# Controller.net
KiCad netlist of a schematic drawn in EAGLE
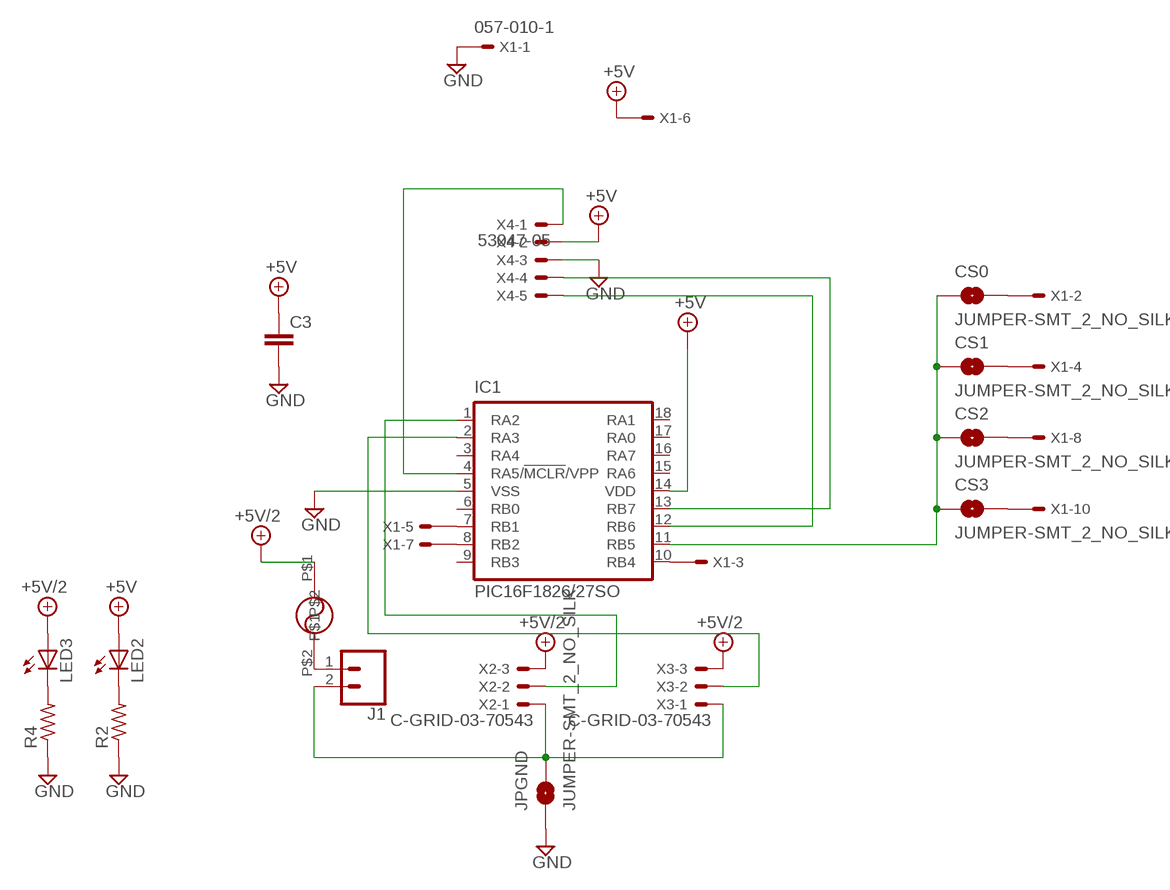
[diagram p0: schematic, sheet 1]

(export (version "E")
  (design (tool "Eeschema 10.0.6"))
  (components
    (comp (ref "C3")
      (value "C-EUC1206")
      (footprint "eagle-import:C1206")
      (libsource (lib "eagle-import") (part "C-EUC1206"))
    )
    (comp (ref "CS0")
      (value "JUMPER-SMT_2_NO_SILK")
      (footprint "eagle-import:SMT-JUMPER_2_NO_SILK")
      (libsource (lib "eagle-import") (part "JUMPER-SMT_2_NO_SILK"))
    )
    (comp (ref "CS1")
      (value "JUMPER-SMT_2_NO_SILK")
      (footprint "eagle-import:SMT-JUMPER_2_NO_SILK")
      (libsource (lib "eagle-import") (part "JUMPER-SMT_2_NO_SILK"))
    )
    (comp (ref "CS2")
      (value "JUMPER-SMT_2_NO_SILK")
      (footprint "eagle-import:SMT-JUMPER_2_NO_SILK")
      (libsource (lib "eagle-import") (part "JUMPER-SMT_2_NO_SILK"))
    )
    (comp (ref "CS3")
      (value "JUMPER-SMT_2_NO_SILK")
      (footprint "eagle-import:SMT-JUMPER_2_NO_SILK")
      (libsource (lib "eagle-import") (part "JUMPER-SMT_2_NO_SILK"))
    )
    (comp (ref "IC1")
      (value "PIC16F1826/27SO")
      (footprint "eagle-import:SO-18W")
      (libsource (lib "eagle-import") (part "PIC16F1826/27SO"))
    )
    (comp (ref "J1")
      (value "CONN_023.5MM")
      (footprint "eagle-import:SCREWTERMINAL-3.5MM-2")
      (libsource (lib "eagle-import") (part "CONN_023.5MM"))
    )
    (comp (ref "JPGND")
      (value "JUMPER-SMT_2_NO_SILK")
      (footprint "eagle-import:SMT-JUMPER_2_NO_SILK")
      (libsource (lib "eagle-import") (part "JUMPER-SMT_2_NO_SILK"))
    )
    (comp (ref "LED2")
      (value "LEDCHIPLED_1206")
      (footprint "eagle-import:CHIPLED_1206")
      (libsource (lib "eagle-import") (part "LEDCHIPLED_1206"))
    )
    (comp (ref "LED3")
      (value "LEDCHIPLED_1206")
      (footprint "eagle-import:CHIPLED_1206")
      (libsource (lib "eagle-import") (part "LEDCHIPLED_1206"))
    )
    (comp (ref "R2")
      (value "R-US_R1206")
      (footprint "eagle-import:R1206")
      (libsource (lib "eagle-import") (part "R-US_R1206"))
    )
    (comp (ref "R4")
      (value "R-US_R1206")
      (footprint "eagle-import:R1206")
      (libsource (lib "eagle-import") (part "R-US_R1206"))
    )
    (comp (ref "U$3")
      (value "0034.6081")
      (footprint "eagle-import:MSF250")
      (libsource (lib "eagle-import") (part "0034.6081"))
    )
    (comp (ref "X1")
      (value "057-010-1")
      (footprint "eagle-import:057-010-1")
      (libsource (lib "eagle-import") (part "057-010-1"))
    )
    (comp (ref "X2")
      (value "C-GRID-03-70543")
      (footprint "eagle-import:70543-03")
      (libsource (lib "eagle-import") (part "C-GRID-03-70543"))
    )
    (comp (ref "X3")
      (value "C-GRID-03-70543")
      (footprint "eagle-import:70543-03")
      (libsource (lib "eagle-import") (part "C-GRID-03-70543"))
    )
    (comp (ref "X4")
      (value "53047-05")
      (footprint "eagle-import:53047-05")
      (fields (field (name "MF") "MOLEX") (field (name "MPN") "53047-0510"))
      (libsource (lib "eagle-import") (part "53?-05047"))
    )
  )
  (nets
    (net (code "1") (name "+5V") (class "Default")
      (node (ref "C3") (pin "1") (pinfunction "1_1") (pintype "passive"))
      (node (ref "IC1") (pin "14") (pinfunction "VDD_14") (pintype "power_in"))
      (node (ref "LED2") (pin "A") (pinfunction "A_A") (pintype "passive"))
      (node (ref "X1") (pin "6") (pinfunction "S_6") (pintype "passive"))
      (node (ref "X4") (pin "2") (pinfunction "S_2") (pintype "passive"))
    )
    (net (code "2") (name "+5V{slash}2") (class "Default")
      (node (ref "LED3") (pin "A") (pinfunction "A_A") (pintype "passive"))
      (node (ref "U$3") (pin "P$1") (pinfunction "P$1_P$1") (pintype "bidirectional"))
      (node (ref "X2") (pin "3") (pinfunction "S_3") (pintype "passive"))
      (node (ref "X3") (pin "3") (pinfunction "S_3") (pintype "passive"))
    )
    (net (code "3") (name "GND") (class "Default")
      (node (ref "C3") (pin "2") (pinfunction "2_2") (pintype "passive"))
      (node (ref "IC1") (pin "5") (pinfunction "VSS_5") (pintype "power_in"))
      (node (ref "JPGND") (pin "1") (pinfunction "1_1") (pintype "passive"))
      (node (ref "R2") (pin "1") (pinfunction "1_1") (pintype "passive"))
      (node (ref "R4") (pin "1") (pinfunction "1_1") (pintype "passive"))
      (node (ref "X1") (pin "1") (pinfunction "S_1") (pintype "passive"))
      (node (ref "X4") (pin "3") (pinfunction "S_3") (pintype "passive"))
    )
    (net (code "4") (name "Net-(IC1-RA2)") (class "Default")
      (node (ref "IC1") (pin "1") (pinfunction "RA2_1") (pintype "bidirectional"))
      (node (ref "X2") (pin "2") (pinfunction "S_2") (pintype "passive"))
    )
    (net (code "5") (name "Net-(IC1-RA3)") (class "Default")
      (node (ref "IC1") (pin "2") (pinfunction "RA3_2") (pintype "bidirectional"))
      (node (ref "X3") (pin "2") (pinfunction "S_2") (pintype "passive"))
    )
    (net (code "6") (name "Net-(IC1-RA5{slash}~{MCLR}{slash}VPP)") (class "Default")
      (node (ref "IC1") (pin "4") (pinfunction "RA5/~{MCLR}/VPP_4") (pintype "bidirectional"))
      (node (ref "X4") (pin "1") (pinfunction "S_1") (pintype "passive"))
    )
    (net (code "7") (name "Net-(IC1-RB1)") (class "Default")
      (node (ref "IC1") (pin "7") (pinfunction "RB1_7") (pintype "bidirectional"))
      (node (ref "X1") (pin "5") (pinfunction "S_5") (pintype "passive"))
    )
    (net (code "8") (name "Net-(IC1-RB2)") (class "Default")
      (node (ref "IC1") (pin "8") (pinfunction "RB2_8") (pintype "bidirectional"))
      (node (ref "X1") (pin "7") (pinfunction "S_7") (pintype "passive"))
    )
    (net (code "9") (name "Net-(IC1-RB4)") (class "Default")
      (node (ref "IC1") (pin "10") (pinfunction "RB4_10") (pintype "bidirectional"))
      (node (ref "X1") (pin "3") (pinfunction "S_3") (pintype "passive"))
    )
    (net (code "10") (name "Net-(IC1-RB5)") (class "Default")
      (node (ref "CS0") (pin "1") (pinfunction "1_1") (pintype "passive"))
      (node (ref "CS1") (pin "1") (pinfunction "1_1") (pintype "passive"))
      (node (ref "CS2") (pin "1") (pinfunction "1_1") (pintype "passive"))
      (node (ref "CS3") (pin "1") (pinfunction "1_1") (pintype "passive"))
      (node (ref "IC1") (pin "11") (pinfunction "RB5_11") (pintype "bidirectional"))
    )
    (net (code "11") (name "Net-(IC1-RB6)") (class "Default")
      (node (ref "IC1") (pin "12") (pinfunction "RB6_12") (pintype "bidirectional"))
      (node (ref "X4") (pin "5") (pinfunction "S_5") (pintype "passive"))
    )
    (net (code "12") (name "Net-(IC1-RB7)") (class "Default")
      (node (ref "IC1") (pin "13") (pinfunction "RB7_13") (pintype "bidirectional"))
      (node (ref "X4") (pin "4") (pinfunction "S_4") (pintype "passive"))
    )
    (net (code "13") (name "Net-(J1-Pad1)") (class "Default")
      (node (ref "J1") (pin "1") (pinfunction "1_1") (pintype "passive"))
      (node (ref "U$3") (pin "P$2") (pinfunction "P$2_P$2") (pintype "bidirectional"))
    )
    (net (code "14") (name "Net-(LED2-PadC)") (class "Default")
      (node (ref "LED2") (pin "C") (pinfunction "C_C") (pintype "passive"))
      (node (ref "R2") (pin "2") (pinfunction "2_2") (pintype "passive"))
    )
    (net (code "15") (name "Net-(LED3-PadC)") (class "Default")
      (node (ref "LED3") (pin "C") (pinfunction "C_C") (pintype "passive"))
      (node (ref "R4") (pin "2") (pinfunction "2_2") (pintype "passive"))
    )
    (net (code "16") (name "Net-(X1B-S)") (class "Default")
      (node (ref "CS3") (pin "2") (pinfunction "2_2") (pintype "passive"))
      (node (ref "X1") (pin "10") (pinfunction "S_10") (pintype "passive"))
    )
    (net (code "17") (name "Net-(X1C-S)") (class "Default")
      (node (ref "CS0") (pin "2") (pinfunction "2_2") (pintype "passive"))
      (node (ref "X1") (pin "2") (pinfunction "S_2") (pintype "passive"))
    )
    (net (code "18") (name "Net-(X1E-S)") (class "Default")
      (node (ref "CS1") (pin "2") (pinfunction "2_2") (pintype "passive"))
      (node (ref "X1") (pin "4") (pinfunction "S_4") (pintype "passive"))
    )
    (net (code "19") (name "Net-(X1I-S)") (class "Default")
      (node (ref "CS2") (pin "2") (pinfunction "2_2") (pintype "passive"))
      (node (ref "X1") (pin "8") (pinfunction "S_8") (pintype "passive"))
    )
    (net (code "20") (name "Net-(X2A-S)") (class "Default")
      (node (ref "J1") (pin "2") (pinfunction "2_2") (pintype "passive"))
      (node (ref "JPGND") (pin "2") (pinfunction "2_2") (pintype "passive"))
      (node (ref "X2") (pin "1") (pinfunction "S_1") (pintype "passive"))
      (node (ref "X3") (pin "1") (pinfunction "S_1") (pintype "passive"))
    )
    (net (code "21") (name "unconnected-(IC1-RA0-Pad17)") (class "Default")
      (node (ref "IC1") (pin "17") (pinfunction "RA0_17") (pintype "bidirectional"))
    )
    (net (code "22") (name "unconnected-(IC1-RA1-Pad18)") (class "Default")
      (node (ref "IC1") (pin "18") (pinfunction "RA1_18") (pintype "bidirectional"))
    )
    (net (code "23") (name "unconnected-(IC1-RA4-Pad3)") (class "Default")
      (node (ref "IC1") (pin "3") (pinfunction "RA4_3") (pintype "bidirectional"))
    )
    (net (code "24") (name "unconnected-(IC1-RA6-Pad15)") (class "Default")
      (node (ref "IC1") (pin "15") (pinfunction "RA6_15") (pintype "bidirectional"))
    )
    (net (code "25") (name "unconnected-(IC1-RA7-Pad16)") (class "Default")
      (node (ref "IC1") (pin "16") (pinfunction "RA7_16") (pintype "bidirectional"))
    )
    (net (code "26") (name "unconnected-(IC1-RB0-Pad6)") (class "Default")
      (node (ref "IC1") (pin "6") (pinfunction "RB0_6") (pintype "bidirectional"))
    )
    (net (code "27") (name "unconnected-(IC1-RB3-Pad9)") (class "Default")
      (node (ref "IC1") (pin "9") (pinfunction "RB3_9") (pintype "bidirectional"))
    )
  )
)
